# untitled.net
KiCad netlist of a schematic drawn in EAGLE
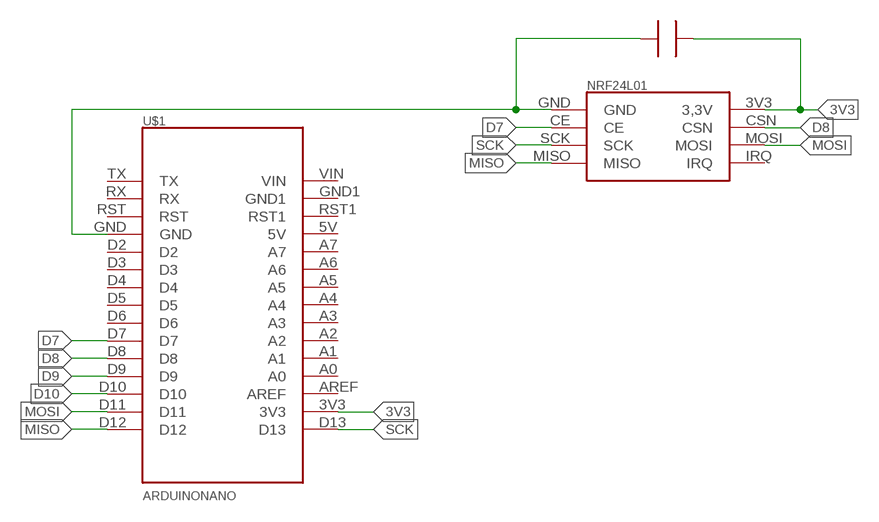
[diagram p0: schematic, sheet 1]

(export (version "E")
  (design (tool "Eeschema 10.0.6"))
  (components
    (comp (ref "U$1")
      (value "ARDUINONANO")
      (footprint "eagle-import:ARDUINONANO")
      (libsource (lib "eagle-import") (part "ARDUINONANO"))
    )
    (comp (ref "U$2") (value "C") (footprint "eagle-import:C") (libsource (lib "eagle-import") (part "C")))
    (comp (ref "U$3")
      (value "NRF24L01")
      (footprint "eagle-import:NRF24L01")
      (libsource (lib "eagle-import") (part "NRF24L01"))
    )
  )
  (nets
    (net (code "1") (name "3V3") (class "Default")
      (node (ref "U$1") (pin "3V3") (pinfunction "3V3_3V3") (pintype "bidirectional"))
      (node (ref "U$2") (pin "+") (pinfunction "+_+") (pintype "bidirectional"))
      (node (ref "U$3") (pin "3V3") (pinfunction "3,3V_3V3") (pintype "bidirectional"))
    )
    (net (code "2") (name "D7") (class "Default")
      (node (ref "U$1") (pin "D7") (pinfunction "D7_D7") (pintype "bidirectional"))
      (node (ref "U$3") (pin "CE") (pinfunction "CE_CE") (pintype "bidirectional"))
    )
    (net (code "3") (name "D8") (class "Default")
      (node (ref "U$1") (pin "D8") (pinfunction "D8_D8") (pintype "bidirectional"))
      (node (ref "U$3") (pin "CSN") (pinfunction "CSN_CSN") (pintype "bidirectional"))
    )
    (net (code "4") (name "D9") (class "Default")
      (node (ref "U$1") (pin "D9") (pinfunction "D9_D9") (pintype "bidirectional"))
    )
    (net (code "5") (name "D10") (class "Default")
      (node (ref "U$1") (pin "D10") (pinfunction "D10_D10") (pintype "bidirectional"))
    )
    (net (code "6") (name "MISO") (class "Default")
      (node (ref "U$1") (pin "D12") (pinfunction "D12_D12") (pintype "bidirectional"))
      (node (ref "U$3") (pin "MISO") (pinfunction "MISO_MISO") (pintype "bidirectional"))
    )
    (net (code "7") (name "MOSI") (class "Default")
      (node (ref "U$1") (pin "D11") (pinfunction "D11_D11") (pintype "bidirectional"))
      (node (ref "U$3") (pin "MOSI") (pinfunction "MOSI_MOSI") (pintype "bidirectional"))
    )
    (net (code "8") (name "Net-(U$1-PadGND)") (class "Default")
      (node (ref "U$1") (pin "GND") (pinfunction "GND_GND") (pintype "bidirectional"))
      (node (ref "U$2") (pin "-") (pinfunction "-_-") (pintype "bidirectional"))
      (node (ref "U$3") (pin "GND") (pinfunction "GND_GND") (pintype "bidirectional"))
    )
    (net (code "9") (name "SCK") (class "Default")
      (node (ref "U$1") (pin "D13") (pinfunction "D13_D13") (pintype "bidirectional"))
      (node (ref "U$3") (pin "SCK") (pinfunction "SCK_SCK") (pintype "bidirectional"))
    )
    (net (code "10") (name "unconnected-(U$1-Pad5V)") (class "Default")
      (node (ref "U$1") (pin "5V") (pinfunction "5V_5V") (pintype "bidirectional"))
    )
    (net (code "11") (name "unconnected-(U$1-PadA0)") (class "Default")
      (node (ref "U$1") (pin "A0") (pinfunction "A0_A0") (pintype "bidirectional"))
    )
    (net (code "12") (name "unconnected-(U$1-PadA1)") (class "Default")
      (node (ref "U$1") (pin "A1") (pinfunction "A1_A1") (pintype "bidirectional"))
    )
    (net (code "13") (name "unconnected-(U$1-PadA2)") (class "Default")
      (node (ref "U$1") (pin "A2") (pinfunction "A2_A2") (pintype "bidirectional"))
    )
    (net (code "14") (name "unconnected-(U$1-PadA3)") (class "Default")
      (node (ref "U$1") (pin "A3") (pinfunction "A3_A3") (pintype "bidirectional"))
    )
    (net (code "15") (name "unconnected-(U$1-PadA4)") (class "Default")
      (node (ref "U$1") (pin "A4") (pinfunction "A4_A4") (pintype "bidirectional"))
    )
    (net (code "16") (name "unconnected-(U$1-PadA5)") (class "Default")
      (node (ref "U$1") (pin "A5") (pinfunction "A5_A5") (pintype "bidirectional"))
    )
    (net (code "17") (name "unconnected-(U$1-PadA6)") (class "Default")
      (node (ref "U$1") (pin "A6") (pinfunction "A6_A6") (pintype "bidirectional"))
    )
    (net (code "18") (name "unconnected-(U$1-PadA7)") (class "Default")
      (node (ref "U$1") (pin "A7") (pinfunction "A7_A7") (pintype "bidirectional"))
    )
    (net (code "19") (name "unconnected-(U$1-PadAREF)") (class "Default")
      (node (ref "U$1") (pin "AREF") (pinfunction "AREF_AREF") (pintype "bidirectional"))
    )
    (net (code "20") (name "unconnected-(U$1-PadD2)") (class "Default")
      (node (ref "U$1") (pin "D2") (pinfunction "D2_D2") (pintype "bidirectional"))
    )
    (net (code "21") (name "unconnected-(U$1-PadD3)") (class "Default")
      (node (ref "U$1") (pin "D3") (pinfunction "D3_D3") (pintype "bidirectional"))
    )
    (net (code "22") (name "unconnected-(U$1-PadD4)") (class "Default")
      (node (ref "U$1") (pin "D4") (pinfunction "D4_D4") (pintype "bidirectional"))
    )
    (net (code "23") (name "unconnected-(U$1-PadD5)") (class "Default")
      (node (ref "U$1") (pin "D5") (pinfunction "D5_D5") (pintype "bidirectional"))
    )
    (net (code "24") (name "unconnected-(U$1-PadD6)") (class "Default")
      (node (ref "U$1") (pin "D6") (pinfunction "D6_D6") (pintype "bidirectional"))
    )
    (net (code "25") (name "unconnected-(U$1-PadGND1)") (class "Default")
      (node (ref "U$1") (pin "GND1") (pinfunction "GND1_GND1") (pintype "bidirectional"))
    )
    (net (code "26") (name "unconnected-(U$1-PadRST)") (class "Default")
      (node (ref "U$1") (pin "RST") (pinfunction "RST_RST") (pintype "bidirectional"))
    )
    (net (code "27") (name "unconnected-(U$1-PadRST1)") (class "Default")
      (node (ref "U$1") (pin "RST1") (pinfunction "RST1_RST1") (pintype "bidirectional"))
    )
    (net (code "28") (name "unconnected-(U$1-PadRX)") (class "Default")
      (node (ref "U$1") (pin "RX") (pinfunction "RX_RX") (pintype "bidirectional"))
    )
    (net (code "29") (name "unconnected-(U$1-PadTX)") (class "Default")
      (node (ref "U$1") (pin "TX") (pinfunction "TX_TX") (pintype "bidirectional"))
    )
    (net (code "30") (name "unconnected-(U$1-PadVIN)") (class "Default")
      (node (ref "U$1") (pin "VIN") (pinfunction "VIN_VIN") (pintype "bidirectional"))
    )
    (net (code "31") (name "unconnected-(U$3-PadIRQ)") (class "Default")
      (node (ref "U$3") (pin "IRQ") (pinfunction "IRQ_IRQ") (pintype "bidirectional"))
    )
  )
)
